# HEATSINK_FAN.net
KiCad netlist of a schematic drawn in Altium Designer
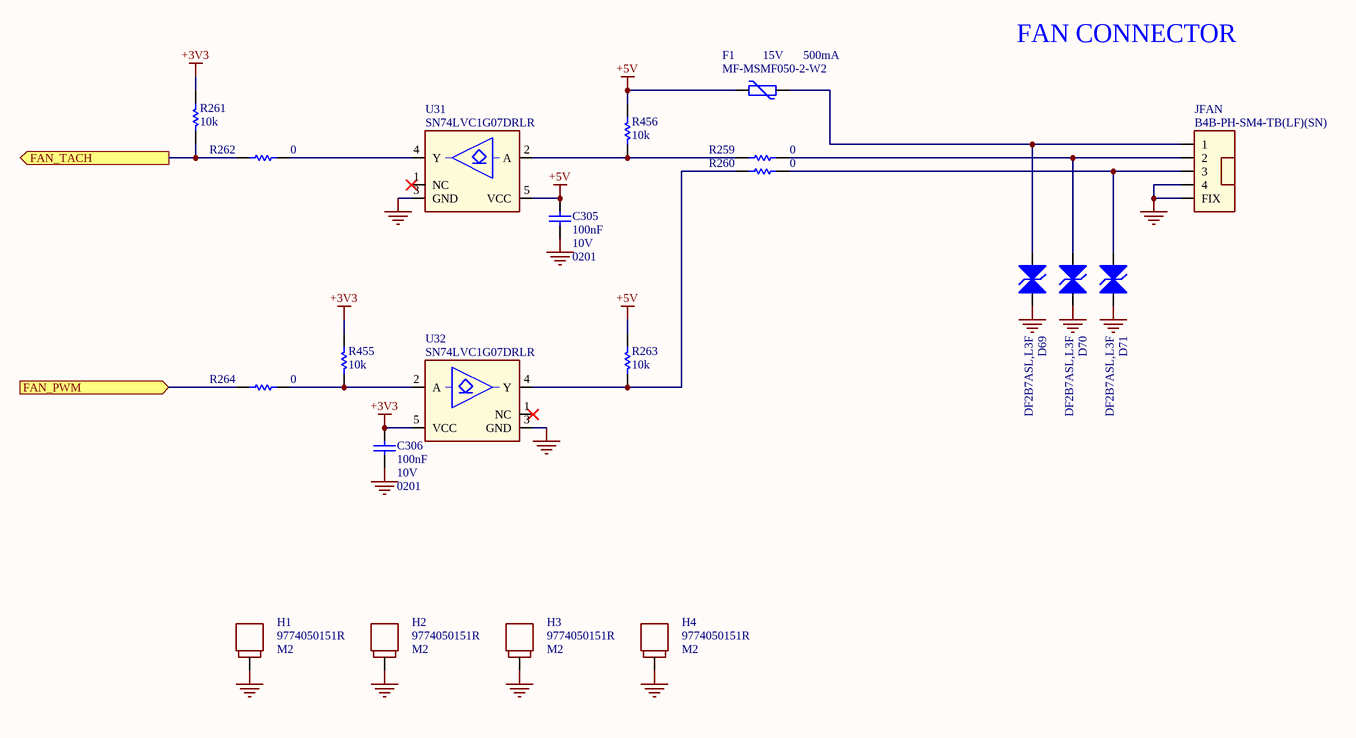
[diagram p0: HEATSINK_FAN.SchDoc]

(export (version "E")
  (design (tool "Eeschema 10.0.6"))
  (components
    (comp (ref "C305")
      (value "100nF")
      (footprint "CAP-0201")
      (description "CAP CHIP 0201 100nF 10% 10V X5R")
      (fields
        (field (name "PART NUMBER") "CL03A104KP3NNNC")
        (field (name "MANUFACTURER") "Samsung Electro-Mechanics")
        (field (name "VOLTAGE") "10V")
        (field (name "CASE CODE (IMPERIAL)") "0201")
      )
      (libsource (lib "Clean") (part "CAP"))
    )
    (comp (ref "C306")
      (value "100nF")
      (footprint "CAP-0201")
      (description "CAP CHIP 0201 100nF 10% 10V X5R")
      (fields
        (field (name "PART NUMBER") "CL03A104KP3NNNC")
        (field (name "MANUFACTURER") "Samsung Electro-Mechanics")
        (field (name "VOLTAGE") "10V")
        (field (name "CASE CODE (IMPERIAL)") "0201")
      )
      (libsource (lib "Clean") (part "CAP"))
    )
    (comp (ref "D69")
      (value "DF2B7ASL,L3F")
      (footprint "DF2B7ASL,L3F")
      (description "TVS BIDIRECTIONAL SMD Vr 5.5V, Vbr min 5.8V, 0.62x0.32mm")
      (fields (field (name "MANUFACTURER") "TOSHIBA"))
      (libsource (lib "Clean") (part "Diode TVS"))
    )
    (comp (ref "D70")
      (value "DF2B7ASL,L3F")
      (footprint "DF2B7ASL,L3F")
      (description "TVS BIDIRECTIONAL SMD Vr 5.5V, Vbr min 5.8V, 0.62x0.32mm")
      (fields (field (name "MANUFACTURER") "TOSHIBA"))
      (libsource (lib "Clean") (part "Diode TVS"))
    )
    (comp (ref "D71")
      (value "DF2B7ASL,L3F")
      (footprint "DF2B7ASL,L3F")
      (description "TVS BIDIRECTIONAL SMD Vr 5.5V, Vbr min 5.8V, 0.62x0.32mm")
      (fields (field (name "MANUFACTURER") "TOSHIBA"))
      (libsource (lib "Clean") (part "Diode TVS"))
    )
    (comp (ref "F1")
      (value "MF-MSMF050-2-W2")
      (footprint "1812")
      (description "PTC RESET FUSE 15V 500MA 1812 LOGO OO ARDUINO")
      (fields
        (field (name "HOLD CURRENT") "500mA")
        (field (name "OPERATING SUPPLY VOLTAGE") "15V")
        (field (name "MANUFACTURER") "Bourns")
      )
      (libsource (lib "Clean") (part "Symbol"))
    )
    (comp (ref "H1")
      (value "9774050151R")
      (footprint "9774050151R")
      (description "M2.5 SPACER SMT ROUND STEEL H=5mm")
      (fields (field (name "MANUFACTURER") "Würth Elektronik"))
      (libsource (lib "Clean") (part "9774050151R"))
    )
    (comp (ref "H2")
      (value "9774050151R")
      (footprint "9774050151R")
      (description "M2.5 SPACER SMT ROUND STEEL H=5mm")
      (fields (field (name "MANUFACTURER") "Würth Elektronik"))
      (libsource (lib "Clean") (part "9774050151R"))
    )
    (comp (ref "H3")
      (value "9774050151R")
      (footprint "9774050151R")
      (description "M2.5 SPACER SMT ROUND STEEL H=5mm")
      (fields (field (name "MANUFACTURER") "Würth Elektronik"))
      (libsource (lib "Clean") (part "9774050151R"))
    )
    (comp (ref "H4")
      (value "9774050151R")
      (footprint "9774050151R")
      (description "M2.5 SPACER SMT ROUND STEEL H=5mm")
      (fields (field (name "MANUFACTURER") "Würth Elektronik"))
      (libsource (lib "Clean") (part "9774050151R"))
    )
    (comp (ref "JFAN")
      (value "B4B-PH-SM4-TB(LF)(SN)")
      (footprint "B4B-PH-SM4-TB(LF)(SN)")
      (description "CONN Header SMD 1x4 vertical polarized")
      (fields (field (name "MANUFACTURER") "JST"))
      (libsource (lib "Clean") (part "SM04B-SRSS-TB(LF)(SN)"))
    )
    (comp (ref "R259")
      (value "0")
      (footprint "RES-0201")
      (description "RES CHIP 0201 0R")
      (fields (field (name "MANUFACTURER") "Vishay") (field (name "PART NUMBER") "CRCW02010000Z0ED"))
      (libsource (lib "Clean") (part "RES"))
    )
    (comp (ref "R260")
      (value "0")
      (footprint "RES-0201")
      (description "RES CHIP 0201 0R")
      (fields (field (name "MANUFACTURER") "Vishay") (field (name "PART NUMBER") "CRCW02010000Z0ED"))
      (libsource (lib "Clean") (part "RES"))
    )
    (comp (ref "R261")
      (value "10k")
      (footprint "RES-0201")
      (description "RES CHIP 0201 10k 1% 1/20W")
      (fields (field (name "POWER") "50mW") (field (name "TOLERANCE") "1%"))
      (libsource (lib "Clean") (part "RES"))
    )
    (comp (ref "R262")
      (value "0")
      (footprint "RES-0201")
      (description "RES CHIP 0201 0R")
      (fields (field (name "MANUFACTURER") "Vishay") (field (name "PART NUMBER") "CRCW02010000Z0ED"))
      (libsource (lib "Clean") (part "RES"))
    )
    (comp (ref "R263")
      (value "10k")
      (footprint "RES-0201")
      (description "RES CHIP 0201 10k 1% 1/20W")
      (fields (field (name "POWER") "50mW") (field (name "TOLERANCE") "1%"))
      (libsource (lib "Clean") (part "RES"))
    )
    (comp (ref "R264")
      (value "0")
      (footprint "RES-0201")
      (description "RES CHIP 0201 0R")
      (fields (field (name "MANUFACTURER") "Vishay") (field (name "PART NUMBER") "CRCW02010000Z0ED"))
      (libsource (lib "Clean") (part "RES"))
    )
    (comp (ref "R455")
      (value "10k")
      (footprint "RES-0201")
      (description "RES CHIP 0201 10k 1% 1/20W")
      (fields (field (name "POWER") "50mW") (field (name "TOLERANCE") "1%"))
      (libsource (lib "Clean") (part "RES"))
    )
    (comp (ref "R456")
      (value "10k")
      (footprint "RES-0201")
      (description "RES CHIP 0201 10k 1% 1/20W")
      (fields (field (name "POWER") "50mW") (field (name "TOLERANCE") "1%"))
      (libsource (lib "Clean") (part "RES"))
    )
    (comp (ref "U31")
      (value "SN74LVC1G07DRLR")
      (footprint "TI DRL DRL0005A")
      (description "IC buffer open drain, 1.65V to 5.5V, 32mA sink current, SOT-5X3 1.6mmx1.6mm")
      (fields (field (name "MANUFACTURER") "Texas Instruments"))
      (libsource (lib "Clean") (part "SN74LVC1G07DRLR"))
    )
    (comp (ref "U32")
      (value "SN74LVC1G07DRLR")
      (footprint "TI DRL DRL0005A")
      (description "IC buffer open drain, 1.65V to 5.5V, 32mA sink current, SOT-5X3 1.6mmx1.6mm")
      (fields (field (name "MANUFACTURER") "Texas Instruments"))
      (libsource (lib "") (part "SN74LVC1G07DRLR_1"))
    )
  )
  (nets
    (net (code "1") (name "+3V3") (class "Default")
      (node (ref "C306") (pin "2") (pinfunction "2_2") (pintype "passive"))
      (node (ref "R261") (pin "2") (pinfunction "2_2") (pintype "passive"))
      (node (ref "R455") (pin "2") (pinfunction "2_2") (pintype "passive"))
      (node (ref "U32") (pin "5") (pinfunction "VCC_5") (pintype "passive"))
    )
    (net (code "2") (name "+5V") (class "Default")
      (node (ref "C305") (pin "2") (pinfunction "2_2") (pintype "passive"))
      (node (ref "F1") (pin "1") (pinfunction "1_1") (pintype "passive"))
      (node (ref "R263") (pin "2") (pinfunction "2_2") (pintype "passive"))
      (node (ref "R456") (pin "2") (pinfunction "2_2") (pintype "passive"))
      (node (ref "U31") (pin "5") (pinfunction "VCC_5") (pintype "passive"))
    )
    (net (code "3") (name "/FAN_PWM") (class "Default")
      (node (ref "R264") (pin "2") (pinfunction "2_2") (pintype "passive"))
    )
    (net (code "4") (name "/FAN_TACH") (class "Default")
      (node (ref "R261") (pin "1") (pinfunction "1_1") (pintype "passive"))
      (node (ref "R262") (pin "2") (pinfunction "2_2") (pintype "passive"))
    )
    (net (code "5") (name "GND") (class "Default")
      (node (ref "C305") (pin "1") (pinfunction "1_1") (pintype "passive"))
      (node (ref "C306") (pin "1") (pinfunction "1_1") (pintype "passive"))
      (node (ref "D69") (pin "1") (pinfunction "A1_1") (pintype "passive"))
      (node (ref "D70") (pin "1") (pinfunction "A1_1") (pintype "passive"))
      (node (ref "D71") (pin "1") (pinfunction "A1_1") (pintype "passive"))
      (node (ref "H1") (pin "1") (pinfunction "1_1") (pintype "passive"))
      (node (ref "H2") (pin "1") (pinfunction "1_1") (pintype "passive"))
      (node (ref "H3") (pin "1") (pinfunction "1_1") (pintype "passive"))
      (node (ref "H4") (pin "1") (pinfunction "1_1") (pintype "passive"))
      (node (ref "JFAN") (pin "4") (pinfunction "4_4") (pintype "passive"))
      (node (ref "JFAN") (pin "FIX") (pinfunction "FIX_FIX") (pintype "passive"))
      (node (ref "U31") (pin "3") (pinfunction "GND_3") (pintype "passive"))
      (node (ref "U32") (pin "3") (pinfunction "GND_3") (pintype "passive"))
    )
    (net (code "6") (name "Net-(D69-A2)") (class "Default")
      (node (ref "D69") (pin "2") (pinfunction "A2_2") (pintype "passive"))
      (node (ref "F1") (pin "2") (pinfunction "2_2") (pintype "passive"))
      (node (ref "JFAN") (pin "1") (pinfunction "1_1") (pintype "passive"))
    )
    (net (code "7") (name "Net-(D70-A2)") (class "Default")
      (node (ref "D70") (pin "2") (pinfunction "A2_2") (pintype "passive"))
      (node (ref "JFAN") (pin "2") (pinfunction "2_2") (pintype "passive"))
      (node (ref "R259") (pin "1") (pinfunction "1_1") (pintype "passive"))
    )
    (net (code "8") (name "Net-(D71-A2)") (class "Default")
      (node (ref "D71") (pin "2") (pinfunction "A2_2") (pintype "passive"))
      (node (ref "JFAN") (pin "3") (pinfunction "3_3") (pintype "passive"))
      (node (ref "R260") (pin "1") (pinfunction "1_1") (pintype "passive"))
    )
    (net (code "9") (name "Net-(U31-A)") (class "Default")
      (node (ref "R259") (pin "2") (pinfunction "2_2") (pintype "passive"))
      (node (ref "R456") (pin "1") (pinfunction "1_1") (pintype "passive"))
      (node (ref "U31") (pin "2") (pinfunction "A_2") (pintype "passive"))
    )
    (net (code "10") (name "Net-(U31-Y)") (class "Default")
      (node (ref "R262") (pin "1") (pinfunction "1_1") (pintype "passive"))
      (node (ref "U31") (pin "4") (pinfunction "Y_4") (pintype "passive"))
    )
    (net (code "11") (name "Net-(U32-A)") (class "Default")
      (node (ref "R264") (pin "1") (pinfunction "1_1") (pintype "passive"))
      (node (ref "R455") (pin "1") (pinfunction "1_1") (pintype "passive"))
      (node (ref "U32") (pin "2") (pinfunction "A_2") (pintype "passive"))
    )
    (net (code "12") (name "Net-(U32-Y)") (class "Default")
      (node (ref "R260") (pin "2") (pinfunction "2_2") (pintype "passive"))
      (node (ref "R263") (pin "1") (pinfunction "1_1") (pintype "passive"))
      (node (ref "U32") (pin "4") (pinfunction "Y_4") (pintype "passive"))
    )
    (net (code "13") (name "unconnected-(U31-NC-Pad1)") (class "Default")
      (node (ref "U31") (pin "1") (pinfunction "NC_1") (pintype "passive+no_connect"))
    )
    (net (code "14") (name "unconnected-(U32-NC-Pad1)") (class "Default")
      (node (ref "U32") (pin "1") (pinfunction "NC_1") (pintype "passive+no_connect"))
    )
  )
)
